# rc2014_can_controller.net
KiCad netlist of a schematic drawn in EAGLE
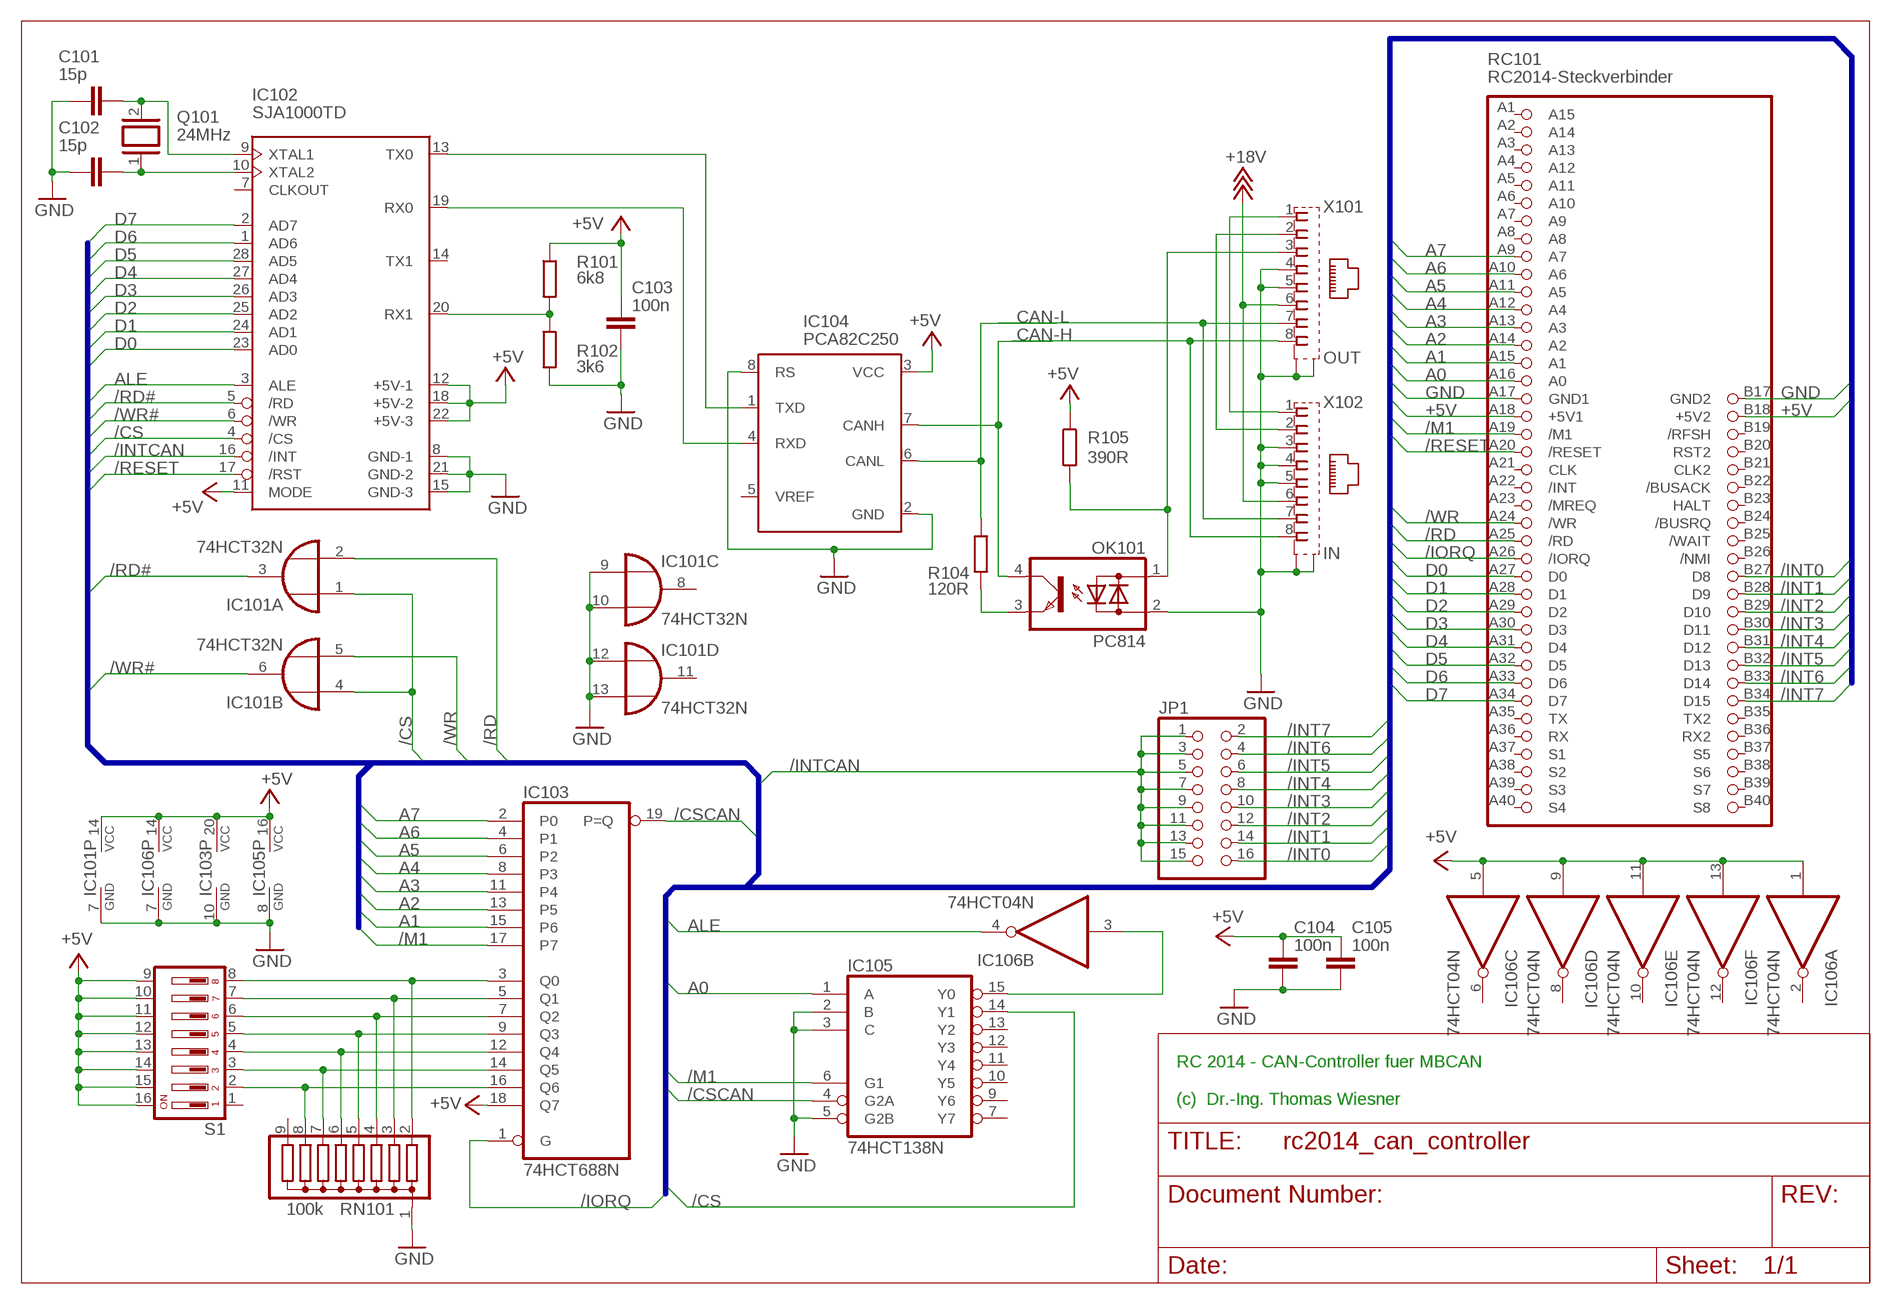
[diagram p0: schematic, sheet 1]

(export (version "E")
  (design (tool "Eeschema 10.0.6"))
  (components
    (comp (ref "C101")
      (value "15p")
      (footprint "eagle-import:C025-025X050")
      (libsource (lib "eagle-import") (part "C-EU025-025X050"))
    )
    (comp (ref "C102")
      (value "15p")
      (footprint "eagle-import:C025-025X050")
      (libsource (lib "eagle-import") (part "C-EU025-025X050"))
    )
    (comp (ref "C103")
      (value "100n")
      (footprint "eagle-import:C025-025X050")
      (libsource (lib "eagle-import") (part "C-EU025-025X050"))
    )
    (comp (ref "C104")
      (value "100n")
      (footprint "eagle-import:C025-025X050")
      (libsource (lib "eagle-import") (part "C-EU025-025X050"))
    )
    (comp (ref "C105")
      (value "100n")
      (footprint "eagle-import:C025-025X050")
      (libsource (lib "eagle-import") (part "C-EU025-025X050"))
    )
    (comp (ref "IC101")
      (value "74HCT32N")
      (footprint "eagle-import:DIL14")
      (libsource (lib "eagle-import") (part "7432NHCT"))
    )
    (comp (ref "IC102")
      (value "SJA1000TD")
      (footprint "eagle-import:DIL28")
      (libsource (lib "eagle-import") (part "SJA1000TD"))
    )
    (comp (ref "IC103")
      (value "74HCT688N")
      (footprint "eagle-import:DIL20")
      (libsource (lib "eagle-import") (part "74688NHCT"))
    )
    (comp (ref "IC104")
      (value "PCA82C250")
      (footprint "eagle-import:DIL08")
      (libsource (lib "eagle-import") (part "PCA82C250"))
    )
    (comp (ref "IC105")
      (value "74HCT138N")
      (footprint "eagle-import:DIL16")
      (libsource (lib "eagle-import") (part "74138NACT"))
    )
    (comp (ref "IC106")
      (value "74HCT04N")
      (footprint "eagle-import:DIL14")
      (libsource (lib "eagle-import") (part "7404NHCT"))
    )
    (comp (ref "JP1")
      (value "PINHD-2X8")
      (footprint "eagle-import:2X08")
      (libsource (lib "eagle-import") (part "PINHD-2X8"))
    )
    (comp (ref "OK101")
      (value "PC814")
      (footprint "eagle-import:DIL04")
      (libsource (lib "eagle-import") (part "PC814"))
    )
    (comp (ref "Q101")
      (value "24MHz")
      (footprint "eagle-import:QS")
      (libsource (lib "eagle-import") (part "XTAL/S"))
    )
    (comp (ref "R101")
      (value "6k8")
      (footprint "eagle-import:0207_10")
      (libsource (lib "eagle-import") (part "R-EU_0207/10"))
    )
    (comp (ref "R102")
      (value "3k6")
      (footprint "eagle-import:0207_10")
      (libsource (lib "eagle-import") (part "R-EU_0207/10"))
    )
    (comp (ref "R104")
      (value "120R")
      (footprint "eagle-import:0207_10")
      (libsource (lib "eagle-import") (part "R-EU_0207/10"))
    )
    (comp (ref "R105")
      (value "390R")
      (footprint "eagle-import:0207_10")
      (libsource (lib "eagle-import") (part "R-EU_0207/10"))
    )
    (comp (ref "RC101")
      (value "RC2014-Steckverbinder")
      (footprint "eagle-import:RC2014-STECKER")
      (libsource (lib "eagle-import") (part "RC2014STECKER"))
    )
    (comp (ref "RN101")
      (value "100k")
      (footprint "eagle-import:SIL9")
      (libsource (lib "eagle-import") (part "G08R"))
    )
    (comp (ref "S1")
      (value "DS08")
      (footprint "eagle-import:DS-08")
      (libsource (lib "eagle-import") (part "DS08"))
    )
    (comp (ref "X101")
      (value "OUT")
      (footprint "eagle-import:0446200002")
      (fields (field (name "MF") "MOLEX") (field (name "MPN") "0446200002"))
      (libsource (lib "eagle-import") (part "0446200002"))
    )
    (comp (ref "X102")
      (value "IN")
      (footprint "eagle-import:0446200002")
      (fields (field (name "MF") "MOLEX") (field (name "MPN") "0446200002"))
      (libsource (lib "eagle-import") (part "0446200002"))
    )
  )
  (nets
    (net (code "1") (name "+5V") (class "Default")
      (node (ref "C103") (pin "2") (pinfunction "2_2") (pintype "passive"))
      (node (ref "C104") (pin "2") (pinfunction "2_2") (pintype "passive"))
      (node (ref "C105") (pin "2") (pinfunction "2_2") (pintype "passive"))
      (node (ref "IC101") (pin "14") (pinfunction "VCC_14") (pintype "power_in"))
      (node (ref "IC102") (pin "11") (pinfunction "MODE_11") (pintype "input"))
      (node (ref "IC102") (pin "12") (pinfunction "+5V-1_12") (pintype "power_in"))
      (node (ref "IC102") (pin "18") (pinfunction "+5V-2_18") (pintype "power_in"))
      (node (ref "IC102") (pin "22") (pinfunction "+5V-3_22") (pintype "power_in"))
      (node (ref "IC103") (pin "18") (pinfunction "Q7_18") (pintype "input"))
      (node (ref "IC103") (pin "20") (pinfunction "VCC_20") (pintype "power_in"))
      (node (ref "IC104") (pin "3") (pinfunction "VCC_3") (pintype "power_in"))
      (node (ref "IC105") (pin "16") (pinfunction "VCC_16") (pintype "power_in"))
      (node (ref "IC106") (pin "1") (pinfunction "I_1") (pintype "input"))
      (node (ref "IC106") (pin "11") (pinfunction "I_11") (pintype "input"))
      (node (ref "IC106") (pin "13") (pinfunction "I_13") (pintype "input"))
      (node (ref "IC106") (pin "14") (pinfunction "VCC_14") (pintype "power_in"))
      (node (ref "IC106") (pin "5") (pinfunction "I_5") (pintype "input"))
      (node (ref "IC106") (pin "9") (pinfunction "I_9") (pintype "input"))
      (node (ref "R101") (pin "1") (pinfunction "1_1") (pintype "passive"))
      (node (ref "R105") (pin "1") (pinfunction "1_1") (pintype "passive"))
      (node (ref "RC101") (pin "A18") (pinfunction "+5V1_A18") (pintype "passive"))
      (node (ref "RC101") (pin "B18") (pinfunction "+5V2_B18") (pintype "passive"))
      (node (ref "S1") (pin "10") (pinfunction "10_10") (pintype "passive"))
      (node (ref "S1") (pin "11") (pinfunction "11_11") (pintype "passive"))
      (node (ref "S1") (pin "12") (pinfunction "12_12") (pintype "passive"))
      (node (ref "S1") (pin "13") (pinfunction "13_13") (pintype "passive"))
      (node (ref "S1") (pin "14") (pinfunction "14_14") (pintype "passive"))
      (node (ref "S1") (pin "15") (pinfunction "15_15") (pintype "passive"))
      (node (ref "S1") (pin "16") (pinfunction "16_16") (pintype "passive"))
      (node (ref "S1") (pin "9") (pinfunction "9_9") (pintype "passive"))
    )
    (net (code "2") (name "+18V") (class "Default")
      (node (ref "X101") (pin "6") (pinfunction "6_6") (pintype "passive"))
      (node (ref "X102") (pin "6") (pinfunction "6_6") (pintype "passive"))
    )
    (net (code "3") (name "/A0") (class "Default")
      (node (ref "IC105") (pin "1") (pinfunction "A_1") (pintype "input"))
      (node (ref "RC101") (pin "A16") (pinfunction "A0_A16") (pintype "passive"))
    )
    (net (code "4") (name "/A1") (class "Default")
      (node (ref "IC103") (pin "15") (pinfunction "P6_15") (pintype "input"))
      (node (ref "RC101") (pin "A15") (pinfunction "A1_A15") (pintype "passive"))
    )
    (net (code "5") (name "/A2") (class "Default")
      (node (ref "IC103") (pin "13") (pinfunction "P5_13") (pintype "input"))
      (node (ref "RC101") (pin "A14") (pinfunction "A2_A14") (pintype "passive"))
    )
    (net (code "6") (name "/A3") (class "Default")
      (node (ref "IC103") (pin "11") (pinfunction "P4_11") (pintype "input"))
      (node (ref "RC101") (pin "A13") (pinfunction "A3_A13") (pintype "passive"))
    )
    (net (code "7") (name "/A4") (class "Default")
      (node (ref "IC103") (pin "8") (pinfunction "P3_8") (pintype "input"))
      (node (ref "RC101") (pin "A12") (pinfunction "A4_A12") (pintype "passive"))
    )
    (net (code "8") (name "/A5") (class "Default")
      (node (ref "IC103") (pin "6") (pinfunction "P2_6") (pintype "input"))
      (node (ref "RC101") (pin "A11") (pinfunction "A5_A11") (pintype "passive"))
    )
    (net (code "9") (name "/A6") (class "Default")
      (node (ref "IC103") (pin "4") (pinfunction "P1_4") (pintype "input"))
      (node (ref "RC101") (pin "A10") (pinfunction "A6_A10") (pintype "passive"))
    )
    (net (code "10") (name "/A7") (class "Default")
      (node (ref "IC103") (pin "2") (pinfunction "P0_2") (pintype "input"))
      (node (ref "RC101") (pin "A9") (pinfunction "A7_A9") (pintype "passive"))
    )
    (net (code "11") (name "/ALE") (class "Default")
      (node (ref "IC102") (pin "3") (pinfunction "ALE_3") (pintype "bidirectional"))
      (node (ref "IC106") (pin "4") (pinfunction "O_4") (pintype "output"))
    )
    (net (code "12") (name "/CAN-H") (class "Default")
      (node (ref "IC104") (pin "7") (pinfunction "CANH_7") (pintype "bidirectional"))
      (node (ref "OK101") (pin "4") (pinfunction "C_4") (pintype "passive"))
      (node (ref "X101") (pin "8") (pinfunction "8_8") (pintype "passive"))
      (node (ref "X102") (pin "8") (pinfunction "8_8") (pintype "passive"))
    )
    (net (code "13") (name "/CAN-L") (class "Default")
      (node (ref "IC104") (pin "6") (pinfunction "CANL_6") (pintype "bidirectional"))
      (node (ref "R104") (pin "2") (pinfunction "2_2") (pintype "passive"))
      (node (ref "X101") (pin "7") (pinfunction "7_7") (pintype "passive"))
      (node (ref "X102") (pin "7") (pinfunction "7_7") (pintype "passive"))
    )
    (net (code "14") (name "/D0") (class "Default")
      (node (ref "IC102") (pin "23") (pinfunction "AD0_23") (pintype "tri_state"))
      (node (ref "RC101") (pin "A27") (pinfunction "D0_A27") (pintype "passive"))
    )
    (net (code "15") (name "/D1") (class "Default")
      (node (ref "IC102") (pin "24") (pinfunction "AD1_24") (pintype "tri_state"))
      (node (ref "RC101") (pin "A28") (pinfunction "D1_A28") (pintype "passive"))
    )
    (net (code "16") (name "/D2") (class "Default")
      (node (ref "IC102") (pin "25") (pinfunction "AD2_25") (pintype "tri_state"))
      (node (ref "RC101") (pin "A29") (pinfunction "D2_A29") (pintype "passive"))
    )
    (net (code "17") (name "/D3") (class "Default")
      (node (ref "IC102") (pin "26") (pinfunction "AD3_26") (pintype "tri_state"))
      (node (ref "RC101") (pin "A30") (pinfunction "D3_A30") (pintype "passive"))
    )
    (net (code "18") (name "/D4") (class "Default")
      (node (ref "IC102") (pin "27") (pinfunction "AD4_27") (pintype "tri_state"))
      (node (ref "RC101") (pin "A31") (pinfunction "D4_A31") (pintype "passive"))
    )
    (net (code "19") (name "/D5") (class "Default")
      (node (ref "IC102") (pin "28") (pinfunction "AD5_28") (pintype "tri_state"))
      (node (ref "RC101") (pin "A32") (pinfunction "D5_A32") (pintype "passive"))
    )
    (net (code "20") (name "/D6") (class "Default")
      (node (ref "IC102") (pin "1") (pinfunction "AD6_1") (pintype "tri_state"))
      (node (ref "RC101") (pin "A33") (pinfunction "D6_A33") (pintype "passive"))
    )
    (net (code "21") (name "/D7") (class "Default")
      (node (ref "IC102") (pin "2") (pinfunction "AD7_2") (pintype "tri_state"))
      (node (ref "RC101") (pin "A34") (pinfunction "D7_A34") (pintype "passive"))
    )
    (net (code "22") (name "/{slash}CS") (class "Default")
      (node (ref "IC101") (pin "1") (pinfunction "I0_1") (pintype "input"))
      (node (ref "IC101") (pin "4") (pinfunction "I0_4") (pintype "input"))
      (node (ref "IC102") (pin "4") (pinfunction "/CS_4") (pintype "input"))
      (node (ref "IC105") (pin "14") (pinfunction "Y1_14") (pintype "output"))
    )
    (net (code "23") (name "/{slash}CSCAN") (class "Default")
      (node (ref "IC103") (pin "19") (pinfunction "P=Q_19") (pintype "output"))
      (node (ref "IC105") (pin "4") (pinfunction "G2A_4") (pintype "input"))
    )
    (net (code "24") (name "/{slash}INT0") (class "Default")
      (node (ref "JP1") (pin "16") (pinfunction "16_16") (pintype "passive"))
      (node (ref "RC101") (pin "B27") (pinfunction "D8_B27") (pintype "passive"))
    )
    (net (code "25") (name "/{slash}INT1") (class "Default")
      (node (ref "JP1") (pin "14") (pinfunction "14_14") (pintype "passive"))
      (node (ref "RC101") (pin "B28") (pinfunction "D9_B28") (pintype "passive"))
    )
    (net (code "26") (name "/{slash}INT2") (class "Default")
      (node (ref "JP1") (pin "12") (pinfunction "12_12") (pintype "passive"))
      (node (ref "RC101") (pin "B29") (pinfunction "D10_B29") (pintype "passive"))
    )
    (net (code "27") (name "/{slash}INT3") (class "Default")
      (node (ref "JP1") (pin "10") (pinfunction "10_10") (pintype "passive"))
      (node (ref "RC101") (pin "B30") (pinfunction "D11_B30") (pintype "passive"))
    )
    (net (code "28") (name "/{slash}INT4") (class "Default")
      (node (ref "JP1") (pin "8") (pinfunction "8_8") (pintype "passive"))
      (node (ref "RC101") (pin "B31") (pinfunction "D12_B31") (pintype "passive"))
    )
    (net (code "29") (name "/{slash}INT5") (class "Default")
      (node (ref "JP1") (pin "6") (pinfunction "6_6") (pintype "passive"))
      (node (ref "RC101") (pin "B32") (pinfunction "D13_B32") (pintype "passive"))
    )
    (net (code "30") (name "/{slash}INT6") (class "Default")
      (node (ref "JP1") (pin "4") (pinfunction "4_4") (pintype "passive"))
      (node (ref "RC101") (pin "B33") (pinfunction "D14_B33") (pintype "passive"))
    )
    (net (code "31") (name "/{slash}INT7") (class "Default")
      (node (ref "JP1") (pin "2") (pinfunction "2_2") (pintype "passive"))
      (node (ref "RC101") (pin "B34") (pinfunction "D15_B34") (pintype "passive"))
    )
    (net (code "32") (name "/{slash}INTCAN") (class "Default")
      (node (ref "IC102") (pin "16") (pinfunction "/INT_16") (pintype "output"))
      (node (ref "JP1") (pin "1") (pinfunction "1_1") (pintype "passive"))
      (node (ref "JP1") (pin "11") (pinfunction "11_11") (pintype "passive"))
      (node (ref "JP1") (pin "13") (pinfunction "13_13") (pintype "passive"))
      (node (ref "JP1") (pin "15") (pinfunction "15_15") (pintype "passive"))
      (node (ref "JP1") (pin "3") (pinfunction "3_3") (pintype "passive"))
      (node (ref "JP1") (pin "5") (pinfunction "5_5") (pintype "passive"))
      (node (ref "JP1") (pin "7") (pinfunction "7_7") (pintype "passive"))
      (node (ref "JP1") (pin "9") (pinfunction "9_9") (pintype "passive"))
    )
    (net (code "33") (name "/{slash}IORQ") (class "Default")
      (node (ref "IC103") (pin "1") (pinfunction "G_1") (pintype "input"))
      (node (ref "RC101") (pin "A26") (pinfunction "/IORQ_A26") (pintype "passive"))
    )
    (net (code "34") (name "/{slash}M1") (class "Default")
      (node (ref "IC103") (pin "17") (pinfunction "P7_17") (pintype "input"))
      (node (ref "IC105") (pin "6") (pinfunction "G1_6") (pintype "input"))
      (node (ref "RC101") (pin "A19") (pinfunction "/M1_A19") (pintype "passive"))
    )
    (net (code "35") (name "/{slash}RD") (class "Default")
      (node (ref "IC101") (pin "2") (pinfunction "I1_2") (pintype "input"))
      (node (ref "RC101") (pin "A25") (pinfunction "/RD_A25") (pintype "passive"))
    )
    (net (code "36") (name "/{slash}RD#") (class "Default")
      (node (ref "IC101") (pin "3") (pinfunction "O_3") (pintype "output"))
      (node (ref "IC102") (pin "5") (pinfunction "/RD_5") (pintype "input"))
    )
    (net (code "37") (name "/{slash}RESET") (class "Default")
      (node (ref "IC102") (pin "17") (pinfunction "/RST_17") (pintype "input"))
      (node (ref "RC101") (pin "A20") (pinfunction "/RESET_A20") (pintype "passive"))
    )
    (net (code "38") (name "/{slash}WR") (class "Default")
      (node (ref "IC101") (pin "5") (pinfunction "I1_5") (pintype "input"))
      (node (ref "RC101") (pin "A24") (pinfunction "/WR_A24") (pintype "passive"))
    )
    (net (code "39") (name "/{slash}WR#") (class "Default")
      (node (ref "IC101") (pin "6") (pinfunction "O_6") (pintype "output"))
      (node (ref "IC102") (pin "6") (pinfunction "/WR_6") (pintype "input"))
    )
    (net (code "40") (name "GND") (class "Default")
      (node (ref "C101") (pin "2") (pinfunction "2_2") (pintype "passive"))
      (node (ref "C102") (pin "2") (pinfunction "2_2") (pintype "passive"))
      (node (ref "C103") (pin "1") (pinfunction "1_1") (pintype "passive"))
      (node (ref "C104") (pin "1") (pinfunction "1_1") (pintype "passive"))
      (node (ref "C105") (pin "1") (pinfunction "1_1") (pintype "passive"))
      (node (ref "IC101") (pin "10") (pinfunction "I1_10") (pintype "input"))
      (node (ref "IC101") (pin "12") (pinfunction "I0_12") (pintype "input"))
      (node (ref "IC101") (pin "13") (pinfunction "I1_13") (pintype "input"))
      (node (ref "IC101") (pin "7") (pinfunction "GND_7") (pintype "power_in"))
      (node (ref "IC101") (pin "9") (pinfunction "I0_9") (pintype "input"))
      (node (ref "IC102") (pin "15") (pinfunction "GND-3_15") (pintype "power_in"))
      (node (ref "IC102") (pin "21") (pinfunction "GND-2_21") (pintype "power_in"))
      (node (ref "IC102") (pin "8") (pinfunction "GND-1_8") (pintype "power_in"))
      (node (ref "IC103") (pin "10") (pinfunction "GND_10") (pintype "power_in"))
      (node (ref "IC104") (pin "2") (pinfunction "GND_2") (pintype "power_in"))
      (node (ref "IC104") (pin "8") (pinfunction "RS_8") (pintype "input"))
      (node (ref "IC105") (pin "2") (pinfunction "B_2") (pintype "input"))
      (node (ref "IC105") (pin "3") (pinfunction "C_3") (pintype "input"))
      (node (ref "IC105") (pin "5") (pinfunction "G2B_5") (pintype "input"))
      (node (ref "IC105") (pin "8") (pinfunction "GND_8") (pintype "power_in"))
      (node (ref "IC106") (pin "7") (pinfunction "GND_7") (pintype "power_in"))
      (node (ref "OK101") (pin "2") (pinfunction "AC2_2") (pintype "passive"))
      (node (ref "R102") (pin "1") (pinfunction "1_1") (pintype "passive"))
      (node (ref "RC101") (pin "A17") (pinfunction "GND1_A17") (pintype "passive"))
      (node (ref "RC101") (pin "B17") (pinfunction "GND2_B17") (pintype "passive"))
      (node (ref "RN101") (pin "1") (pinfunction "1_1") (pintype "passive"))
      (node (ref "X101") (pin "4") (pinfunction "4_4") (pintype "passive"))
      (node (ref "X101") (pin "5") (pinfunction "5_5") (pintype "passive"))
      (node (ref "X101") (pin "S@1") (pinfunction "S1_S@1") (pintype "passive"))
      (node (ref "X101") (pin "S@2") (pinfunction "S2_S@2") (pintype "passive"))
      (node (ref "X102") (pin "3") (pinfunction "3_3") (pintype "passive"))
      (node (ref "X102") (pin "4") (pinfunction "4_4") (pintype "passive"))
      (node (ref "X102") (pin "5") (pinfunction "5_5") (pintype "passive"))
      (node (ref "X102") (pin "S@1") (pinfunction "S1_S@1") (pintype "passive"))
      (node (ref "X102") (pin "S@2") (pinfunction "S2_S@2") (pintype "passive"))
    )
    (net (code "41") (name "Net-(IC102-RX0)") (class "Default")
      (node (ref "IC102") (pin "19") (pinfunction "RX0_19") (pintype "input"))
      (node (ref "IC104") (pin "4") (pinfunction "RXD_4") (pintype "output"))
    )
    (net (code "42") (name "Net-(IC102-RX1)") (class "Default")
      (node (ref "IC102") (pin "20") (pinfunction "RX1_20") (pintype "input"))
      (node (ref "R101") (pin "2") (pinfunction "2_2") (pintype "passive"))
      (node (ref "R102") (pin "2") (pinfunction "2_2") (pintype "passive"))
    )
    (net (code "43") (name "Net-(IC102-TX0)") (class "Default")
      (node (ref "IC102") (pin "13") (pinfunction "TX0_13") (pintype "output"))
      (node (ref "IC104") (pin "1") (pinfunction "TXD_1") (pintype "input"))
    )
    (net (code "44") (name "Net-(IC102-XTAL1)") (class "Default")
      (node (ref "C101") (pin "1") (pinfunction "1_1") (pintype "passive"))
      (node (ref "IC102") (pin "9") (pinfunction "XTAL1_9") (pintype "input"))
      (node (ref "Q101") (pin "2") (pinfunction "2_2") (pintype "passive"))
    )
    (net (code "45") (name "Net-(IC102-XTAL2)") (class "Default")
      (node (ref "C102") (pin "1") (pinfunction "1_1") (pintype "passive"))
      (node (ref "IC102") (pin "10") (pinfunction "XTAL2_10") (pintype "output"))
      (node (ref "Q101") (pin "1") (pinfunction "1_1") (pintype "passive"))
    )
    (net (code "46") (name "Net-(IC103A-Q0)") (class "Default")
      (node (ref "IC103") (pin "3") (pinfunction "Q0_3") (pintype "input"))
      (node (ref "RN101") (pin "2") (pinfunction "2_2") (pintype "passive"))
      (node (ref "S1") (pin "8") (pinfunction "8_8") (pintype "passive"))
    )
    (net (code "47") (name "Net-(IC103A-Q1)") (class "Default")
      (node (ref "IC103") (pin "5") (pinfunction "Q1_5") (pintype "input"))
      (node (ref "RN101") (pin "3") (pinfunction "3_3") (pintype "passive"))
      (node (ref "S1") (pin "7") (pinfunction "7_7") (pintype "passive"))
    )
    (net (code "48") (name "Net-(IC103A-Q2)") (class "Default")
      (node (ref "IC103") (pin "7") (pinfunction "Q2_7") (pintype "input"))
      (node (ref "RN101") (pin "4") (pinfunction "4_4") (pintype "passive"))
      (node (ref "S1") (pin "6") (pinfunction "6_6") (pintype "passive"))
    )
    (net (code "49") (name "Net-(IC103A-Q3)") (class "Default")
      (node (ref "IC103") (pin "9") (pinfunction "Q3_9") (pintype "input"))
      (node (ref "RN101") (pin "5") (pinfunction "5_5") (pintype "passive"))
      (node (ref "S1") (pin "5") (pinfunction "5_5") (pintype "passive"))
    )
    (net (code "50") (name "Net-(IC103A-Q4)") (class "Default")
      (node (ref "IC103") (pin "12") (pinfunction "Q4_12") (pintype "input"))
      (node (ref "RN101") (pin "6") (pinfunction "6_6") (pintype "passive"))
      (node (ref "S1") (pin "4") (pinfunction "4_4") (pintype "passive"))
    )
    (net (code "51") (name "Net-(IC103A-Q5)") (class "Default")
      (node (ref "IC103") (pin "14") (pinfunction "Q5_14") (pintype "input"))
      (node (ref "RN101") (pin "7") (pinfunction "7_7") (pintype "passive"))
      (node (ref "S1") (pin "3") (pinfunction "3_3") (pintype "passive"))
    )
    (net (code "52") (name "Net-(IC103A-Q6)") (class "Default")
      (node (ref "IC103") (pin "16") (pinfunction "Q6_16") (pintype "input"))
      (node (ref "RN101") (pin "8") (pinfunction "8_8") (pintype "passive"))
      (node (ref "S1") (pin "2") (pinfunction "2_2") (pintype "passive"))
    )
    (net (code "53") (name "Net-(IC105A-Y0)") (class "Default")
      (node (ref "IC105") (pin "15") (pinfunction "Y0_15") (pintype "output"))
      (node (ref "IC106") (pin "3") (pinfunction "I_3") (pintype "input"))
    )
    (net (code "54") (name "Net-(OK101-AC1)") (class "Default")
      (node (ref "OK101") (pin "1") (pinfunction "AC1_1") (pintype "passive"))
      (node (ref "R105") (pin "2") (pinfunction "2_2") (pintype "passive"))
      (node (ref "X101") (pin "3") (pinfunction "3_3") (pintype "passive"))
    )
    (net (code "55") (name "Net-(OK101-E)") (class "Default")
      (node (ref "OK101") (pin "3") (pinfunction "E_3") (pintype "passive"))
      (node (ref "R104") (pin "1") (pinfunction "1_1") (pintype "passive"))
    )
    (net (code "56") (name "Net-(X101-Pad1)") (class "Default")
      (node (ref "X101") (pin "1") (pinfunction "1_1") (pintype "passive"))
      (node (ref "X102") (pin "1") (pinfunction "1_1") (pintype "passive"))
    )
    (net (code "57") (name "Net-(X101-Pad2)") (class "Default")
      (node (ref "X101") (pin "2") (pinfunction "2_2") (pintype "passive"))
      (node (ref "X102") (pin "2") (pinfunction "2_2") (pintype "passive"))
    )
    (net (code "58") (name "unconnected-(IC101C-O-Pad8)") (class "Default")
      (node (ref "IC101") (pin "8") (pinfunction "O_8") (pintype "output"))
    )
    (net (code "59") (name "unconnected-(IC101D-O-Pad11)") (class "Default")
      (node (ref "IC101") (pin "11") (pinfunction "O_11") (pintype "output"))
    )
    (net (code "60") (name "unconnected-(IC102-CLKOUT-Pad7)") (class "Default")
      (node (ref "IC102") (pin "7") (pinfunction "CLKOUT_7") (pintype "output"))
    )
    (net (code "61") (name "unconnected-(IC102-TX1-Pad14)") (class "Default")
      (node (ref "IC102") (pin "14") (pinfunction "TX1_14") (pintype "output"))
    )
    (net (code "62") (name "unconnected-(IC104-VREF-Pad5)") (class "Default")
      (node (ref "IC104") (pin "5") (pinfunction "VREF_5") (pintype "output"))
    )
    (net (code "63") (name "unconnected-(IC105A-Y2-Pad13)") (class "Default")
      (node (ref "IC105") (pin "13") (pinfunction "Y2_13") (pintype "output"))
    )
    (net (code "64") (name "unconnected-(IC105A-Y3-Pad12)") (class "Default")
      (node (ref "IC105") (pin "12") (pinfunction "Y3_12") (pintype "output"))
    )
    (net (code "65") (name "unconnected-(IC105A-Y4-Pad11)") (class "Default")
      (node (ref "IC105") (pin "11") (pinfunction "Y4_11") (pintype "output"))
    )
    (net (code "66") (name "unconnected-(IC105A-Y5-Pad10)") (class "Default")
      (node (ref "IC105") (pin "10") (pinfunction "Y5_10") (pintype "output"))
    )
    (net (code "67") (name "unconnected-(IC105A-Y6-Pad9)") (class "Default")
      (node (ref "IC105") (pin "9") (pinfunction "Y6_9") (pintype "output"))
    )
    (net (code "68") (name "unconnected-(IC105A-Y7-Pad7)") (class "Default")
      (node (ref "IC105") (pin "7") (pinfunction "Y7_7") (pintype "output"))
    )
    (net (code "69") (name "unconnected-(IC106A-O-Pad2)") (class "Default")
      (node (ref "IC106") (pin "2") (pinfunction "O_2") (pintype "output"))
    )
    (net (code "70") (name "unconnected-(IC106C-O-Pad6)") (class "Default")
      (node (ref "IC106") (pin "6") (pinfunction "O_6") (pintype "output"))
    )
    (net (code "71") (name "unconnected-(IC106D-O-Pad8)") (class "Default")
      (node (ref "IC106") (pin "8") (pinfunction "O_8") (pintype "output"))
    )
    (net (code "72") (name "unconnected-(IC106E-O-Pad10)") (class "Default")
      (node (ref "IC106") (pin "10") (pinfunction "O_10") (pintype "output"))
    )
    (net (code "73") (name "unconnected-(IC106F-O-Pad12)") (class "Default")
      (node (ref "IC106") (pin "12") (pinfunction "O_12") (pintype "output"))
    )
    (net (code "74") (name "unconnected-(RC101-A9-PadA7)") (class "Default")
      (node (ref "RC101") (pin "A7") (pinfunction "A9_A7") (pintype "passive"))
    )
    (net (code "75") (name "unconnected-(RC101-A10-PadA6)") (class "Default")
      (node (ref "RC101") (pin "A6") (pinfunction "A10_A6") (pintype "passive"))
    )
    (net (code "76") (name "unconnected-(RC101-A11-PadA5)") (class "Default")
      (node (ref "RC101") (pin "A5") (pinfunction "A11_A5") (pintype "passive"))
    )
    (net (code "77") (name "unconnected-(RC101-A12-PadA4)") (class "Default")
      (node (ref "RC101") (pin "A4") (pinfunction "A12_A4") (pintype "passive"))
    )
    (net (code "78") (name "unconnected-(RC101-A13-PadA3)") (class "Default")
      (node (ref "RC101") (pin "A3") (pinfunction "A13_A3") (pintype "passive"))
    )
    (net (code "79") (name "unconnected-(RC101-A14-PadA2)") (class "Default")
      (node (ref "RC101") (pin "A2") (pinfunction "A14_A2") (pintype "passive"))
    )
    (net (code "80") (name "unconnected-(RC101-A15-PadA1)") (class "Default")
      (node (ref "RC101") (pin "A1") (pinfunction "A15_A1") (pintype "passive"))
    )
    (net (code "81") (name "unconnected-(RC101-CLK-PadA21)") (class "Default")
      (node (ref "RC101") (pin "A21") (pinfunction "CLK_A21") (pintype "passive"))
    )
    (net (code "82") (name "unconnected-(RC101-CLK2-PadB21)") (class "Default")
      (node (ref "RC101") (pin "B21") (pinfunction "CLK2_B21") (pintype "passive"))
    )
    (net (code "83") (name "unconnected-(RC101-HALT-PadB23)") (class "Default")
      (node (ref "RC101") (pin "B23") (pinfunction "HALT_B23") (pintype "passive"))
    )
    (net (code "84") (name "unconnected-(RC101-PadA8)") (class "Default")
      (node (ref "RC101") (pin "A8") (pinfunction "A8_A8") (pintype "passive"))
    )
    (net (code "85") (name "unconnected-(RC101-RST2-PadB20)") (class "Default")
      (node (ref "RC101") (pin "B20") (pinfunction "RST2_B20") (pintype "passive"))
    )
    (net (code "86") (name "unconnected-(RC101-RX-PadA36)") (class "Default")
      (node (ref "RC101") (pin "A36") (pinfunction "RX_A36") (pintype "passive"))
    )
    (net (code "87") (name "unconnected-(RC101-RX2-PadB36)") (class "Default")
      (node (ref "RC101") (pin "B36") (pinfunction "RX2_B36") (pintype "passive"))
    )
    (net (code "88") (name "unconnected-(RC101-S1-PadA37)") (class "Default")
      (node (ref "RC101") (pin "A37") (pinfunction "S1_A37") (pintype "passive"))
    )
    (net (code "89") (name "unconnected-(RC101-S2-PadA38)") (class "Default")
      (node (ref "RC101") (pin "A38") (pinfunction "S2_A38") (pintype "passive"))
    )
    (net (code "90") (name "unconnected-(RC101-S3-PadA39)") (class "Default")
      (node (ref "RC101") (pin "A39") (pinfunction "S3_A39") (pintype "passive"))
    )
    (net (code "91") (name "unconnected-(RC101-S4-PadA40)") (class "Default")
      (node (ref "RC101") (pin "A40") (pinfunction "S4_A40") (pintype "passive"))
    )
    (net (code "92") (name "unconnected-(RC101-S5-PadB37)") (class "Default")
      (node (ref "RC101") (pin "B37") (pinfunction "S5_B37") (pintype "passive"))
    )
    (net (code "93") (name "unconnected-(RC101-S6-PadB38)") (class "Default")
      (node (ref "RC101") (pin "B38") (pinfunction "S6_B38") (pintype "passive"))
    )
    (net (code "94") (name "unconnected-(RC101-S7-PadB39)") (class "Default")
      (node (ref "RC101") (pin "B39") (pinfunction "S7_B39") (pintype "passive"))
    )
    (net (code "95") (name "unconnected-(RC101-S8-PadB40)") (class "Default")
      (node (ref "RC101") (pin "B40") (pinfunction "S8_B40") (pintype "passive"))
    )
    (net (code "96") (name "unconnected-(RC101-TX-PadA35)") (class "Default")
      (node (ref "RC101") (pin "A35") (pinfunction "TX_A35") (pintype "passive"))
    )
    (net (code "97") (name "unconnected-(RC101-TX2-PadB35)") (class "Default")
      (node (ref "RC101") (pin "B35") (pinfunction "TX2_B35") (pintype "passive"))
    )
    (net (code "98") (name "unconnected-(RC101-{slash}BUSACK-PadB22)") (class "Default")
      (node (ref "RC101") (pin "B22") (pinfunction "/BUSACK_B22") (pintype "passive"))
    )
    (net (code "99") (name "unconnected-(RC101-{slash}BUSRQ-PadB24)") (class "Default")
      (node (ref "RC101") (pin "B24") (pinfunction "/BUSRQ_B24") (pintype "passive"))
    )
    (net (code "100") (name "unconnected-(RC101-{slash}INT-PadA22)") (class "Default")
      (node (ref "RC101") (pin "A22") (pinfunction "/INT_A22") (pintype "passive"))
    )
    (net (code "101") (name "unconnected-(RC101-{slash}MREQ-PadA23)") (class "Default")
      (node (ref "RC101") (pin "A23") (pinfunction "/MREQ_A23") (pintype "passive"))
    )
    (net (code "102") (name "unconnected-(RC101-{slash}NMI-PadB26)") (class "Default")
      (node (ref "RC101") (pin "B26") (pinfunction "/NMI_B26") (pintype "passive"))
    )
    (net (code "103") (name "unconnected-(RC101-{slash}RFSH-PadB19)") (class "Default")
      (node (ref "RC101") (pin "B19") (pinfunction "/RFSH_B19") (pintype "passive"))
    )
    (net (code "104") (name "unconnected-(RC101-{slash}WAIT-PadB25)") (class "Default")
      (node (ref "RC101") (pin "B25") (pinfunction "/WAIT_B25") (pintype "passive"))
    )
    (net (code "105") (name "unconnected-(RN101-Pad9)") (class "Default")
      (node (ref "RN101") (pin "9") (pinfunction "9_9") (pintype "passive"))
    )
    (net (code "106") (name "unconnected-(S1-Pad1)") (class "Default")
      (node (ref "S1") (pin "1") (pinfunction "1_1") (pintype "passive"))
    )
  )
)
